# M.net
KiCad netlist of a schematic drawn in Altium Designer
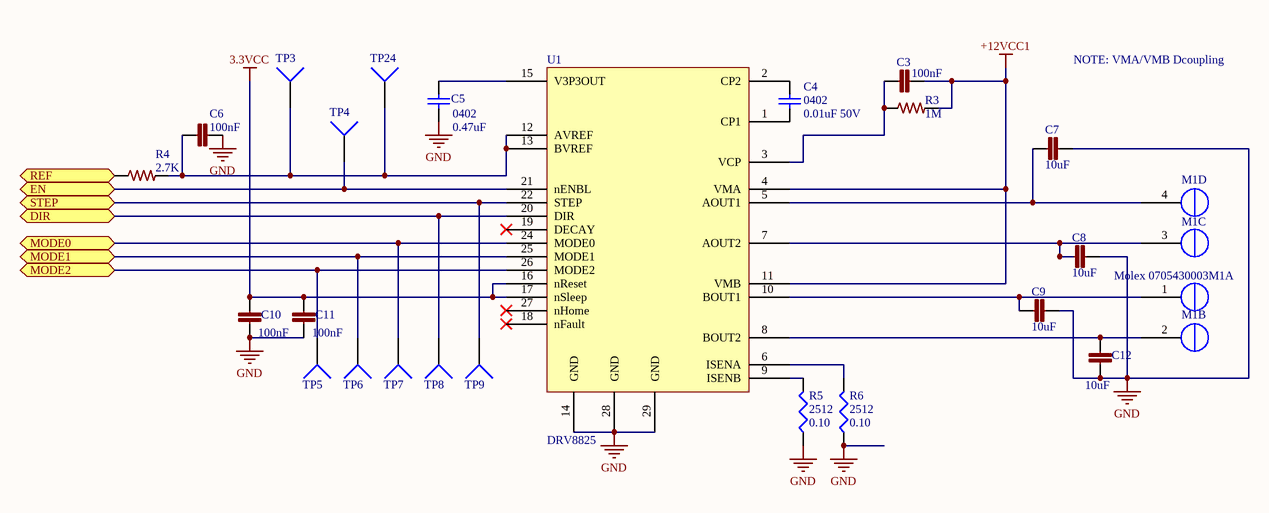
[diagram p0: M.SchDoc]

(export (version "E")
  (design (tool "Eeschema 10.0.6"))
  (components
    (comp (ref "C3")
      (value "100nF")
      (footprint "C0603")
      (description "CAP CER 0603 100nF 50V 10% X7R")
      (fields
        (field (name "MANUFACTURERPARTNUMBER") "C0603C104K5RACTU")
        (field (name "PUBLISHER") "UltiMachine")
      )
      (libsource (lib "3Delight") (part "C0603C104K5RACTU"))
    )
    (comp (ref "C4")
      (value "0.01uF 50V")
      (footprint "C0402")
      (description "CAP CER 10000PF 50V X7R 0402")
      (fields
        (field (name "MFR PART #") "GRM155R71H103JA88D")
        (field (name "MFR") "Murata")
        (field (name "PACKAGEREFERENCE") "0402")
        (field (name "PUBLISHER") "Ultimachine")
      )
      (libsource (lib "Tigershark3D") (part "GRM155R71H103JA88D"))
    )
    (comp (ref "C5")
      (value "0.47uF")
      (footprint "C0402")
      (description "0.47uF 6.3v C0402 - GRM155R60J474KE19D")
      (fields
        (field (name "MFR PART #") "GRM155R60J474KE19D")
        (field (name "MFR") "Murata")
        (field (name "PACKAGEREFERENCE") "0402")
        (field (name "PUBLISHER") "Ultimachine")
      )
      (libsource (lib "Tigershark3D") (part "GRM155R60J474KE19D"))
    )
    (comp (ref "C6")
      (value "100nF")
      (footprint "C0402")
      (description "CAP CER 0402 100nF 16V 10% X7R")
      (fields
        (field (name "MANUFACTURERPARTNUMBER") "GRM155R71C104KA88D")
        (field (name "PUBLISHER") "UltiMachine")
      )
      (libsource (lib "") (part "GRM155R71C104KA88D_1"))
    )
    (comp (ref "C7")
      (value "10uF")
      (footprint "C0603")
      (description "CAP CER 0603 1uF 10V Y5V")
      (fields
        (field (name "MANUFACTURERPARTNUMBER") "CC0603ZRY5V6BB105")
        (field (name "PUBLISHER") "UltiMachine")
      )
      (libsource (lib "") (part "CC0603ZRY5V6BB105_1"))
    )
    (comp (ref "C8")
      (value "10uF")
      (footprint "C0603")
      (description "CAP CER 0603 1uF 10V Y5V")
      (fields
        (field (name "MANUFACTURERPARTNUMBER") "CC0603ZRY5V6BB105")
        (field (name "PUBLISHER") "UltiMachine")
      )
      (libsource (lib "") (part "CC0603ZRY5V6BB105_1"))
    )
    (comp (ref "C9")
      (value "10uF")
      (footprint "C0603")
      (description "CAP CER 0603 1uF 10V Y5V")
      (fields
        (field (name "MANUFACTURERPARTNUMBER") "CC0603ZRY5V6BB105")
        (field (name "PUBLISHER") "UltiMachine")
      )
      (libsource (lib "") (part "CC0603ZRY5V6BB105_1"))
    )
    (comp (ref "C10")
      (value "100nF")
      (footprint "C0402")
      (description "CAP CER 0402 100nF 16V 10% X7R")
      (fields
        (field (name "MANUFACTURERPARTNUMBER") "GRM155R71C104KA88D")
        (field (name "PUBLISHER") "UltiMachine")
      )
      (libsource (lib "3Delight") (part "GRM155R71C104KA88D"))
    )
    (comp (ref "C11")
      (value "100nF")
      (footprint "C0402")
      (description "CAP CER 0402 100nF 16V 10% X7R")
      (fields
        (field (name "MANUFACTURERPARTNUMBER") "GRM155R71C104KA88D")
        (field (name "PUBLISHER") "UltiMachine")
      )
      (libsource (lib "3Delight") (part "GRM155R71C104KA88D"))
    )
    (comp (ref "C12")
      (value "10uF")
      (footprint "C0603")
      (description "CAP CER 0603 1uF 10V Y5V")
      (fields
        (field (name "MANUFACTURERPARTNUMBER") "CC0603ZRY5V6BB105")
        (field (name "PUBLISHER") "UltiMachine")
      )
      (libsource (lib "Tigershark3D") (part "CC0603ZRY5V6BB105"))
    )
    (comp (ref "M1")
      (value "Molex 0705430003")
      (footprint "4POL254")
      (description "Molex 4 Pin Clip Connector")
      (libsource (lib "ZMBo Schematic Library") (part "Molex 0705430003 Alt"))
    )
    (comp (ref "R3")
      (value "1M")
      (footprint "R0402")
      (description "RES 0402 1M 100mW 5%")
      (fields (field (name "MANUFACTURERPARTNUMBER") "ERJ2GEJ105X") (field (name "PUBLISHER") "UltiMachine"))
      (libsource (lib "Tigershark3D") (part "ERJ2GEJ105X"))
    )
    (comp (ref "R4")
      (value "2.7K")
      (footprint "R0402")
      (description "RES SMD 2.7K OHM 1% 1/10W 0402")
      (fields
        (field (name "MANUFACTURER") "Panasonic")
        (field (name "MANUFACTURERPARTNUMBER") "ERJ2GEJ105X")
        (field (name "PUBLISHER") "Adam")
      )
      (libsource (lib "Tigershark3D") (part "ERJ-2RKF2701X"))
    )
    (comp (ref "R5")
      (value "2512")
      (footprint "2512R-0.55")
      (description "RES SMD 0.1 OHM 1% 2W 2512")
      (fields (field (name "MFR") "Stackpole ELectronics Inc") (field (name "ALTIUM_VALUE") "0.10"))
      (libsource (lib "Tigershark3D") (part "CSRN2512FTR100"))
    )
    (comp (ref "R6")
      (value "2512")
      (footprint "2512R-0.55")
      (description "RES SMD 0.1 OHM 1% 2W 2512")
      (fields (field (name "MFR") "Stackpole ELectronics Inc") (field (name "ALTIUM_VALUE") "0.10"))
      (libsource (lib "Tigershark3D") (part "CSRN2512FTR100"))
    )
    (comp (ref "TP3")
      (value "TP4")
      (footprint "TP-2")
      (description "Socket")
      (fields (field (name "PUBLISHER") "Altium Limited"))
      (libsource (lib "ZMBo Schematic Library") (part "Socket"))
    )
    (comp (ref "TP4")
      (value "TP4")
      (footprint "TP-2")
      (description "Socket")
      (fields (field (name "PUBLISHER") "Altium Limited"))
      (libsource (lib "ZMBo Schematic Library") (part "Socket"))
    )
    (comp (ref "TP5")
      (value "TP4")
      (footprint "TP-2")
      (description "Socket")
      (fields (field (name "PUBLISHER") "Altium Limited"))
      (libsource (lib "ZMBo Schematic Library") (part "Socket"))
    )
    (comp (ref "TP6")
      (value "TP4")
      (footprint "TP-2")
      (description "Socket")
      (fields (field (name "PUBLISHER") "Altium Limited"))
      (libsource (lib "ZMBo Schematic Library") (part "Socket"))
    )
    (comp (ref "TP7")
      (value "TP4")
      (footprint "TP-2")
      (description "Socket")
      (fields (field (name "PUBLISHER") "Altium Limited"))
      (libsource (lib "ZMBo Schematic Library") (part "Socket"))
    )
    (comp (ref "TP8")
      (value "TP4")
      (footprint "TP-2")
      (description "Socket")
      (fields (field (name "PUBLISHER") "Altium Limited"))
      (libsource (lib "ZMBo Schematic Library") (part "Socket"))
    )
    (comp (ref "TP9")
      (value "TP4")
      (footprint "TP-2")
      (description "Socket")
      (fields (field (name "PUBLISHER") "Altium Limited"))
      (libsource (lib "ZMBo Schematic Library") (part "Socket"))
    )
    (comp (ref "TP24")
      (value "TP4")
      (footprint "TP-2")
      (description "Socket")
      (fields (field (name "PUBLISHER") "Altium Limited"))
      (libsource (lib "ZMBo Schematic Library") (part "Socket"))
    )
    (comp (ref "U1")
      (value "DRV8825")
      (footprint "DRV8825PWPR")
      (description "DRV8825 Ti Stepper Driver")
      (fields (field (name "PART NUMBER") "DRV8825PWPR") (field (name "VOLTAGE") "8.2-45VDC"))
      (libsource (lib "Tigershark3D") (part "DRV8825"))
    )
  )
  (nets
    (net (code "1") (name "+12VCC1") (class "Default")
      (node (ref "C3") (pin "2") (pinfunction "2_2") (pintype "passive"))
      (node (ref "R3") (pin "2") (pinfunction "2_2") (pintype "passive"))
      (node (ref "U1") (pin "11") (pinfunction "VMB_11") (pintype "passive"))
      (node (ref "U1") (pin "4") (pinfunction "VMA_4") (pintype "passive"))
    )
    (net (code "2") (name "/DIR") (class "Default")
      (node (ref "TP8") (pin "1") (pinfunction "1_1") (pintype "passive"))
      (node (ref "U1") (pin "20") (pinfunction "DIR_20") (pintype "passive"))
    )
    (net (code "3") (name "/EN") (class "Default")
      (node (ref "TP4") (pin "1") (pinfunction "1_1") (pintype "passive"))
      (node (ref "U1") (pin "21") (pinfunction "nENBL_21") (pintype "passive"))
    )
    (net (code "4") (name "/MODE0") (class "Default")
      (node (ref "TP7") (pin "1") (pinfunction "1_1") (pintype "passive"))
      (node (ref "U1") (pin "24") (pinfunction "MODE0_24") (pintype "passive"))
    )
    (net (code "5") (name "/MODE1") (class "Default")
      (node (ref "TP6") (pin "1") (pinfunction "1_1") (pintype "passive"))
      (node (ref "U1") (pin "25") (pinfunction "MODE1_25") (pintype "passive"))
    )
    (net (code "6") (name "/MODE2") (class "Default")
      (node (ref "TP5") (pin "1") (pinfunction "1_1") (pintype "passive"))
      (node (ref "U1") (pin "26") (pinfunction "MODE2_26") (pintype "passive"))
    )
    (net (code "7") (name "/REF") (class "Default")
      (node (ref "R4") (pin "1") (pinfunction "1_1") (pintype "passive"))
    )
    (net (code "8") (name "/STEP") (class "Default")
      (node (ref "TP9") (pin "1") (pinfunction "1_1") (pintype "passive"))
      (node (ref "U1") (pin "22") (pinfunction "STEP_22") (pintype "passive"))
    )
    (net (code "9") (name "3.3VCC") (class "Default")
      (node (ref "C10") (pin "1") (pinfunction "1_1") (pintype "passive"))
      (node (ref "C11") (pin "1") (pinfunction "1_1") (pintype "passive"))
      (node (ref "U1") (pin "16") (pinfunction "nReset_16") (pintype "passive"))
      (node (ref "U1") (pin "17") (pinfunction "nSleep_17") (pintype "passive"))
    )
    (net (code "10") (name "GND") (class "Default")
      (node (ref "C10") (pin "2") (pinfunction "2_2") (pintype "passive"))
      (node (ref "C11") (pin "2") (pinfunction "2_2") (pintype "passive"))
      (node (ref "C12") (pin "2") (pinfunction "2_2") (pintype "passive"))
      (node (ref "C5") (pin "1") (pinfunction "1_1") (pintype "passive"))
      (node (ref "C6") (pin "1") (pinfunction "1_1") (pintype "passive"))
      (node (ref "C7") (pin "2") (pinfunction "2_2") (pintype "passive"))
      (node (ref "C8") (pin "2") (pinfunction "2_2") (pintype "passive"))
      (node (ref "C9") (pin "2") (pinfunction "2_2") (pintype "passive"))
      (node (ref "R5") (pin "1") (pinfunction "1_1") (pintype "passive"))
      (node (ref "R6") (pin "1") (pinfunction "1_1") (pintype "passive"))
      (node (ref "U1") (pin "14") (pinfunction "GND_14") (pintype "passive"))
      (node (ref "U1") (pin "28") (pinfunction "GND_28") (pintype "passive"))
      (node (ref "U1") (pin "29") (pinfunction "GND_29") (pintype "passive"))
    )
    (net (code "11") (name "Net-(M1A-OUT2B)") (class "Default")
      (node (ref "C9") (pin "1") (pinfunction "1_1") (pintype "passive"))
      (node (ref "M1") (pin "1") (pinfunction "OUT2B_1") (pintype "passive"))
      (node (ref "U1") (pin "10") (pinfunction "BOUT1_10") (pintype "passive"))
    )
    (net (code "12") (name "Net-(M1B-OUT2A)") (class "Default")
      (node (ref "C12") (pin "1") (pinfunction "1_1") (pintype "passive"))
      (node (ref "M1") (pin "2") (pinfunction "OUT2A_2") (pintype "passive"))
      (node (ref "U1") (pin "8") (pinfunction "BOUT2_8") (pintype "passive"))
    )
    (net (code "13") (name "Net-(M1C-OUT1A)") (class "Default")
      (node (ref "C8") (pin "1") (pinfunction "1_1") (pintype "passive"))
      (node (ref "M1") (pin "3") (pinfunction "OUT1A_3") (pintype "passive"))
      (node (ref "U1") (pin "7") (pinfunction "AOUT2_7") (pintype "passive"))
    )
    (net (code "14") (name "Net-(M1D-OUT1B)") (class "Default")
      (node (ref "C7") (pin "1") (pinfunction "1_1") (pintype "passive"))
      (node (ref "M1") (pin "4") (pinfunction "OUT1B_4") (pintype "passive"))
      (node (ref "U1") (pin "5") (pinfunction "AOUT1_5") (pintype "passive"))
    )
    (net (code "15") (name "Net-(U1-AVREF)") (class "Default")
      (node (ref "C6") (pin "2") (pinfunction "2_2") (pintype "passive"))
      (node (ref "R4") (pin "2") (pinfunction "2_2") (pintype "passive"))
      (node (ref "TP24") (pin "1") (pinfunction "1_1") (pintype "passive"))
      (node (ref "TP3") (pin "1") (pinfunction "1_1") (pintype "passive"))
      (node (ref "U1") (pin "12") (pinfunction "AVREF_12") (pintype "passive"))
      (node (ref "U1") (pin "13") (pinfunction "BVREF_13") (pintype "passive"))
    )
    (net (code "16") (name "Net-(U1-CP1)") (class "Default")
      (node (ref "C4") (pin "1") (pinfunction "1_1") (pintype "passive"))
      (node (ref "U1") (pin "1") (pinfunction "CP1_1") (pintype "passive"))
    )
    (net (code "17") (name "Net-(U1-CP2)") (class "Default")
      (node (ref "C4") (pin "2") (pinfunction "2_2") (pintype "passive"))
      (node (ref "U1") (pin "2") (pinfunction "CP2_2") (pintype "passive"))
    )
    (net (code "18") (name "Net-(U1-ISENA)") (class "Default")
      (node (ref "R6") (pin "2") (pinfunction "2_2") (pintype "passive"))
      (node (ref "U1") (pin "6") (pinfunction "ISENA_6") (pintype "passive"))
    )
    (net (code "19") (name "Net-(U1-ISENB)") (class "Default")
      (node (ref "R5") (pin "2") (pinfunction "2_2") (pintype "passive"))
      (node (ref "U1") (pin "9") (pinfunction "ISENB_9") (pintype "passive"))
    )
    (net (code "20") (name "Net-(U1-V3P3OUT)") (class "Default")
      (node (ref "C5") (pin "2") (pinfunction "2_2") (pintype "passive"))
      (node (ref "U1") (pin "15") (pinfunction "V3P3OUT_15") (pintype "passive"))
    )
    (net (code "21") (name "Net-(U1-VCP)") (class "Default")
      (node (ref "C3") (pin "1") (pinfunction "1_1") (pintype "passive"))
      (node (ref "R3") (pin "1") (pinfunction "1_1") (pintype "passive"))
      (node (ref "U1") (pin "3") (pinfunction "VCP_3") (pintype "passive"))
    )
    (net (code "22") (name "unconnected-(U1-DECAY-Pad19)") (class "Default")
      (node (ref "U1") (pin "19") (pinfunction "DECAY_19") (pintype "passive+no_connect"))
    )
    (net (code "23") (name "unconnected-(U1-NC-Pad23)") (class "Default")
      (node (ref "U1") (pin "23") (pinfunction "NC_23") (pintype "passive"))
    )
    (net (code "24") (name "unconnected-(U1-nFault-Pad18)") (class "Default")
      (node (ref "U1") (pin "18") (pinfunction "nFault_18") (pintype "passive+no_connect"))
    )
    (net (code "25") (name "unconnected-(U1-nHome-Pad27)") (class "Default")
      (node (ref "U1") (pin "27") (pinfunction "nHome_27") (pintype "passive+no_connect"))
    )
  )
)
